# rgbpi-sch.net
KiCad netlist of a schematic drawn in EAGLE
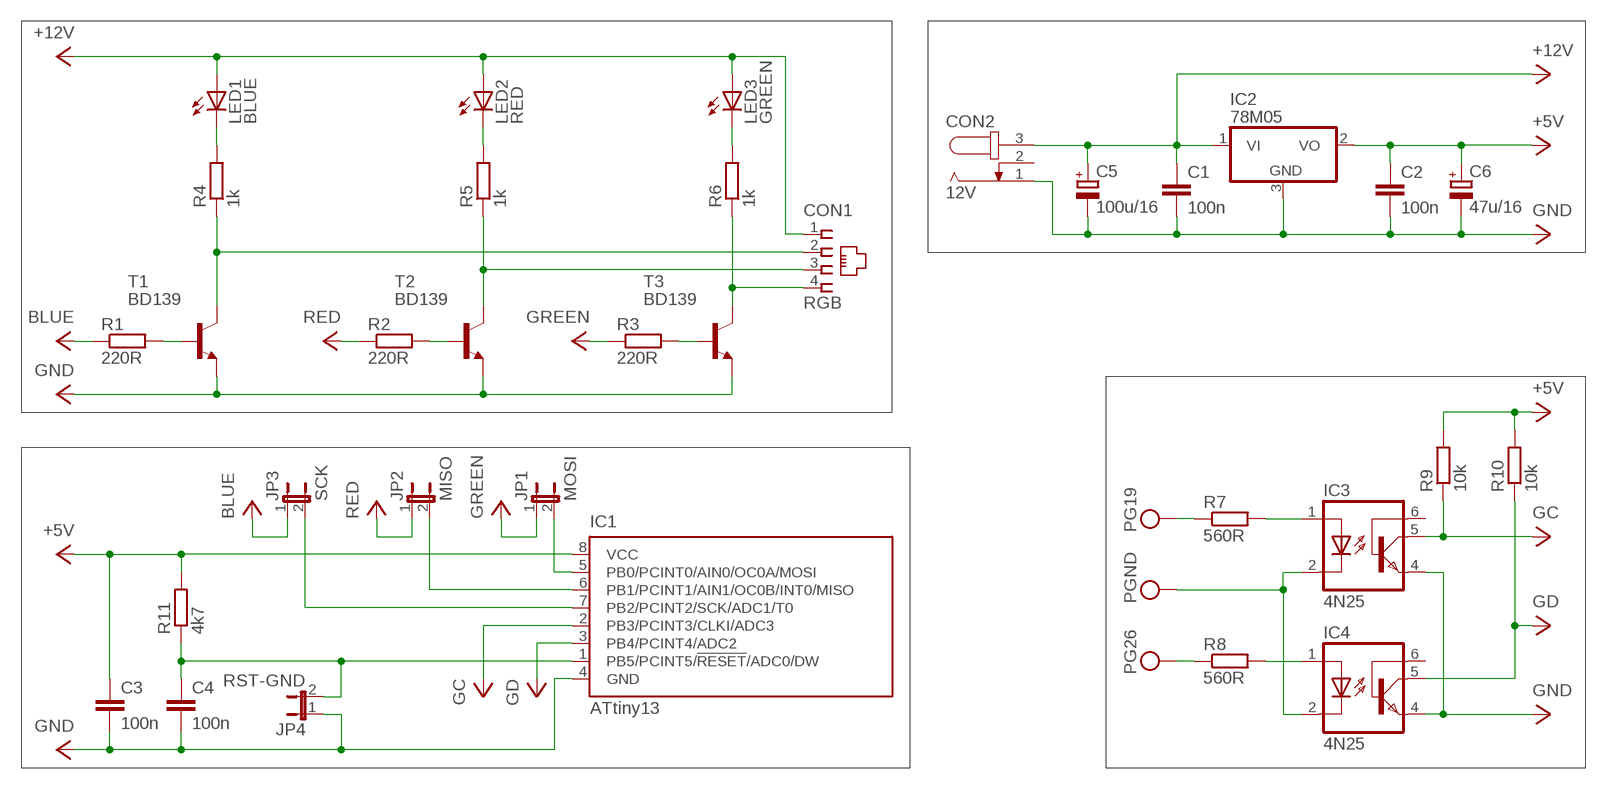
[diagram p0: schematic, sheet 1]

(export (version "E")
  (design (tool "Eeschema 10.0.6"))
  (components
    (comp (ref "C1")
      (value "100n")
      (footprint "eagle-import:C2.5-3")
      (libsource (lib "eagle-import") (part "C2,5-3"))
    )
    (comp (ref "C2")
      (value "100n")
      (footprint "eagle-import:C2.5-3")
      (libsource (lib "eagle-import") (part "C2,5-3"))
    )
    (comp (ref "C3")
      (value "100n")
      (footprint "eagle-import:C2.5-3")
      (libsource (lib "eagle-import") (part "C2,5-3"))
    )
    (comp (ref "C4")
      (value "100n")
      (footprint "eagle-import:C2.5-3")
      (libsource (lib "eagle-import") (part "C2,5-3"))
    )
    (comp (ref "C5")
      (value "100u/16")
      (footprint "eagle-import:085CS_1AR")
      (libsource (lib "eagle-import") (part "CPOL-EU085CS-1AR"))
    )
    (comp (ref "C6")
      (value "47u/16")
      (footprint "eagle-import:085CS_1AR")
      (libsource (lib "eagle-import") (part "CPOL-EU085CS-1AR"))
    )
    (comp (ref "CON1")
      (value "RGB")
      (footprint "eagle-import:215875-3")
      (libsource (lib "eagle-import") (part "215875-3"))
    )
    (comp (ref "CON2")
      (value "12V")
      (footprint "eagle-import:SPC4077")
      (libsource (lib "eagle-import") (part "JACK-PLUG0"))
    )
    (comp (ref "IC1")
      (value "ATtiny13")
      (footprint "eagle-import:8S1")
      (fields (field (name "MPN") "ATTINY13-20SSU"))
      (libsource (lib "eagle-import") (part "TINY13SSU-20"))
    )
    (comp (ref "IC2")
      (value "78M05")
      (footprint "eagle-import:TO252")
      (libsource (lib "eagle-import") (part "78DT05"))
    )
    (comp (ref "IC3")
      (value "4N25")
      (footprint "eagle-import:DIL06")
      (fields (field (name "MPN") "4N25-M"))
      (libsource (lib "eagle-import") (part "4N?M25"))
    )
    (comp (ref "IC4")
      (value "4N25")
      (footprint "eagle-import:DIL06")
      (fields (field (name "MPN") "4N25-M"))
      (libsource (lib "eagle-import") (part "4N?M25"))
    )
    (comp (ref "JP1")
      (value "MOSI")
      (footprint "eagle-import:JP1")
      (libsource (lib "eagle-import") (part "JP1E"))
    )
    (comp (ref "JP2")
      (value "MISO")
      (footprint "eagle-import:JP1")
      (libsource (lib "eagle-import") (part "JP1E"))
    )
    (comp (ref "JP3")
      (value "SCK")
      (footprint "eagle-import:JP1")
      (libsource (lib "eagle-import") (part "JP1E"))
    )
    (comp (ref "JP4")
      (value "RST-GND")
      (footprint "eagle-import:JP1")
      (libsource (lib "eagle-import") (part "JP1E"))
    )
    (comp (ref "LED1")
      (value "BLUE")
      (footprint "eagle-import:W57B")
      (libsource (lib "eagle-import") (part "W57BLA"))
    )
    (comp (ref "LED2")
      (value "RED")
      (footprint "eagle-import:W57B")
      (libsource (lib "eagle-import") (part "W57BLA"))
    )
    (comp (ref "LED3")
      (value "GREEN")
      (footprint "eagle-import:W57B")
      (libsource (lib "eagle-import") (part "W57BLA"))
    )
    (comp (ref "R1")
      (value "220R")
      (footprint "eagle-import:R0805")
      (libsource (lib "eagle-import") (part "R"))
    )
    (comp (ref "R2")
      (value "220R")
      (footprint "eagle-import:R0805")
      (libsource (lib "eagle-import") (part "R"))
    )
    (comp (ref "R3")
      (value "220R")
      (footprint "eagle-import:R0805")
      (libsource (lib "eagle-import") (part "R"))
    )
    (comp (ref "R4")
      (value "1k")
      (footprint "eagle-import:R0805")
      (libsource (lib "eagle-import") (part "R"))
    )
    (comp (ref "R5")
      (value "1k")
      (footprint "eagle-import:R0805")
      (libsource (lib "eagle-import") (part "R"))
    )
    (comp (ref "R6")
      (value "1k")
      (footprint "eagle-import:R0805")
      (libsource (lib "eagle-import") (part "R"))
    )
    (comp (ref "R7")
      (value "560R")
      (footprint "eagle-import:R0805")
      (libsource (lib "eagle-import") (part "R"))
    )
    (comp (ref "R8")
      (value "560R")
      (footprint "eagle-import:R0805")
      (libsource (lib "eagle-import") (part "R"))
    )
    (comp (ref "R9")
      (value "10k")
      (footprint "eagle-import:R0805")
      (libsource (lib "eagle-import") (part "R"))
    )
    (comp (ref "R10")
      (value "10k")
      (footprint "eagle-import:R0805")
      (libsource (lib "eagle-import") (part "R"))
    )
    (comp (ref "R11")
      (value "4k7")
      (footprint "eagle-import:R0805")
      (libsource (lib "eagle-import") (part "R"))
    )
    (comp (ref "T1")
      (value "BD139")
      (footprint "eagle-import:TO126")
      (libsource (lib "eagle-import") (part "BD139"))
    )
    (comp (ref "T2")
      (value "BD139")
      (footprint "eagle-import:TO126")
      (libsource (lib "eagle-import") (part "BD139"))
    )
    (comp (ref "T3")
      (value "BD139")
      (footprint "eagle-import:TO126")
      (libsource (lib "eagle-import") (part "BD139"))
    )
  )
  (nets
    (net (code "1") (name "+12V") (class "Default")
      (node (ref "C1") (pin "1") (pinfunction "1_1") (pintype "passive"))
      (node (ref "C1") (pin "2") (pinfunction "2_2") (pintype "passive"))
      (node (ref "C2") (pin "1") (pinfunction "1_1") (pintype "passive"))
      (node (ref "C2") (pin "2") (pinfunction "2_2") (pintype "passive"))
      (node (ref "C3") (pin "1") (pinfunction "1_1") (pintype "passive"))
      (node (ref "C3") (pin "2") (pinfunction "2_2") (pintype "passive"))
      (node (ref "C4") (pin "2") (pinfunction "2_2") (pintype "passive"))
      (node (ref "C5") (pin "+") (pinfunction "+_+") (pintype "passive"))
      (node (ref "C5") (pin "-") (pinfunction "-_-") (pintype "passive"))
      (node (ref "C6") (pin "+") (pinfunction "+_+") (pintype "passive"))
      (node (ref "C6") (pin "-") (pinfunction "-_-") (pintype "passive"))
      (node (ref "CON1") (pin "1") (pinfunction "1_1") (pintype "passive"))
      (node (ref "CON2") (pin "1") (pinfunction "1_1") (pintype "passive"))
      (node (ref "CON2") (pin "3") (pinfunction "3_3") (pintype "passive"))
      (node (ref "IC1") (pin "2") (pinfunction "PB3/PCINT3/CLKI/ADC3_2") (pintype "bidirectional"))
      (node (ref "IC1") (pin "3") (pinfunction "PB4/PCINT4/ADC2_3") (pintype "bidirectional"))
      (node (ref "IC1") (pin "4") (pinfunction "GND_4") (pintype "power_in"))
      (node (ref "IC1") (pin "8") (pinfunction "VCC_8") (pintype "power_in"))
      (node (ref "IC2") (pin "1") (pinfunction "VI_1") (pintype "input"))
      (node (ref "IC2") (pin "2") (pinfunction "VO_2") (pintype "passive"))
      (node (ref "IC2") (pin "3") (pinfunction "GND_3") (pintype "passive"))
      (node (ref "IC3") (pin "2") (pinfunction "C_2") (pintype "passive"))
      (node (ref "IC3") (pin "4") (pinfunction "EMI_4") (pintype "passive"))
      (node (ref "IC3") (pin "5") (pinfunction "COL_5") (pintype "passive"))
      (node (ref "IC4") (pin "2") (pinfunction "C_2") (pintype "passive"))
      (node (ref "IC4") (pin "4") (pinfunction "EMI_4") (pintype "passive"))
      (node (ref "IC4") (pin "5") (pinfunction "COL_5") (pintype "passive"))
      (node (ref "JP1") (pin "1") (pinfunction "1_1") (pintype "passive"))
      (node (ref "JP2") (pin "1") (pinfunction "1_1") (pintype "passive"))
      (node (ref "JP3") (pin "1") (pinfunction "1_1") (pintype "passive"))
      (node (ref "JP4") (pin "1") (pinfunction "1_1") (pintype "passive"))
      (node (ref "LED1") (pin "A") (pinfunction "A_A") (pintype "passive"))
      (node (ref "LED2") (pin "A") (pinfunction "A_A") (pintype "passive"))
      (node (ref "LED3") (pin "A") (pinfunction "A_A") (pintype "passive"))
      (node (ref "R1") (pin "1") (pinfunction "1_1") (pintype "passive"))
      (node (ref "R10") (pin "1") (pinfunction "1_1") (pintype "passive"))
      (node (ref "R10") (pin "2") (pinfunction "2_2") (pintype "passive"))
      (node (ref "R11") (pin "2") (pinfunction "2_2") (pintype "passive"))
      (node (ref "R2") (pin "1") (pinfunction "1_1") (pintype "passive"))
      (node (ref "R3") (pin "1") (pinfunction "1_1") (pintype "passive"))
      (node (ref "R7") (pin "1") (pinfunction "1_1") (pintype "passive"))
      (node (ref "R8") (pin "1") (pinfunction "1_1") (pintype "passive"))
      (node (ref "R9") (pin "1") (pinfunction "1_1") (pintype "passive"))
      (node (ref "R9") (pin "2") (pinfunction "2_2") (pintype "passive"))
      (node (ref "T1") (pin "1") (pinfunction "E_1") (pintype "passive"))
      (node (ref "T2") (pin "1") (pinfunction "E_1") (pintype "passive"))
      (node (ref "T3") (pin "1") (pinfunction "E_1") (pintype "passive"))
    )
    (net (code "2") (name "Net-(IC1-PB0{slash}PCINT0{slash}AIN0{slash}OC0A{slash}MOSI)") (class "Default")
      (node (ref "IC1") (pin "5") (pinfunction "PB0/PCINT0/AIN0/OC0A/MOSI_5") (pintype "bidirectional"))
      (node (ref "JP1") (pin "2") (pinfunction "2_2") (pintype "passive"))
    )
    (net (code "3") (name "Net-(IC1-PB1{slash}PCINT1{slash}AIN1{slash}OC0B{slash}INT0{slash}MISO)") (class "Default")
      (node (ref "IC1") (pin "6") (pinfunction "PB1/PCINT1/AIN1/OC0B/INT0/MISO_6") (pintype "bidirectional"))
      (node (ref "JP2") (pin "2") (pinfunction "2_2") (pintype "passive"))
    )
    (net (code "4") (name "Net-(IC1-PB2{slash}PCINT2{slash}SCK{slash}ADC1{slash}T0)") (class "Default")
      (node (ref "IC1") (pin "7") (pinfunction "PB2/PCINT2/SCK/ADC1/T0_7") (pintype "bidirectional"))
      (node (ref "JP3") (pin "2") (pinfunction "2_2") (pintype "passive"))
    )
    (net (code "5") (name "Net-(IC1-PB5{slash}PCINT5{slash}~{RESET}{slash}ADC0{slash}DW)") (class "Default")
      (node (ref "C4") (pin "1") (pinfunction "1_1") (pintype "passive"))
      (node (ref "IC1") (pin "1") (pinfunction "PB5/PCINT5/~{RESET}/ADC0/DW_1") (pintype "bidirectional"))
      (node (ref "JP4") (pin "2") (pinfunction "2_2") (pintype "passive"))
      (node (ref "R11") (pin "1") (pinfunction "1_1") (pintype "passive"))
    )
    (net (code "6") (name "Net-(IC3-A)") (class "Default")
      (node (ref "IC3") (pin "1") (pinfunction "A_1") (pintype "passive"))
      (node (ref "R7") (pin "2") (pinfunction "2_2") (pintype "passive"))
    )
    (net (code "7") (name "Net-(IC4-A)") (class "Default")
      (node (ref "IC4") (pin "1") (pinfunction "A_1") (pintype "passive"))
      (node (ref "R8") (pin "2") (pinfunction "2_2") (pintype "passive"))
    )
    (net (code "8") (name "Net-(LED1-C-PadC@1)") (class "Default")
      (node (ref "LED1") (pin "C") (pinfunction "C_C") (pintype "passive"))
      (node (ref "LED1") (pin "C@1") (pinfunction "C_C@1") (pintype "passive"))
      (node (ref "LED1") (pin "C@2") (pinfunction "C_C@2") (pintype "passive"))
      (node (ref "LED1") (pin "C@3") (pinfunction "C_C@3") (pintype "passive"))
      (node (ref "LED1") (pin "C@4") (pinfunction "C_C@4") (pintype "passive"))
      (node (ref "LED1") (pin "C@5") (pinfunction "C_C@5") (pintype "passive"))
      (node (ref "R4") (pin "2") (pinfunction "2_2") (pintype "passive"))
    )
    (net (code "9") (name "Net-(LED2-C-PadC@1)") (class "Default")
      (node (ref "LED2") (pin "C") (pinfunction "C_C") (pintype "passive"))
      (node (ref "LED2") (pin "C@1") (pinfunction "C_C@1") (pintype "passive"))
      (node (ref "LED2") (pin "C@2") (pinfunction "C_C@2") (pintype "passive"))
      (node (ref "LED2") (pin "C@3") (pinfunction "C_C@3") (pintype "passive"))
      (node (ref "LED2") (pin "C@4") (pinfunction "C_C@4") (pintype "passive"))
      (node (ref "LED2") (pin "C@5") (pinfunction "C_C@5") (pintype "passive"))
      (node (ref "R5") (pin "2") (pinfunction "2_2") (pintype "passive"))
    )
    (net (code "10") (name "Net-(LED3-C-PadC@1)") (class "Default")
      (node (ref "LED3") (pin "C") (pinfunction "C_C") (pintype "passive"))
      (node (ref "LED3") (pin "C@1") (pinfunction "C_C@1") (pintype "passive"))
      (node (ref "LED3") (pin "C@2") (pinfunction "C_C@2") (pintype "passive"))
      (node (ref "LED3") (pin "C@3") (pinfunction "C_C@3") (pintype "passive"))
      (node (ref "LED3") (pin "C@4") (pinfunction "C_C@4") (pintype "passive"))
      (node (ref "LED3") (pin "C@5") (pinfunction "C_C@5") (pintype "passive"))
      (node (ref "R6") (pin "2") (pinfunction "2_2") (pintype "passive"))
    )
    (net (code "11") (name "Net-(T1-B)") (class "Default")
      (node (ref "R1") (pin "2") (pinfunction "2_2") (pintype "passive"))
      (node (ref "T1") (pin "3") (pinfunction "B_3") (pintype "passive"))
    )
    (net (code "12") (name "Net-(T1-C)") (class "Default")
      (node (ref "CON1") (pin "2") (pinfunction "2_2") (pintype "passive"))
      (node (ref "R4") (pin "1") (pinfunction "1_1") (pintype "passive"))
      (node (ref "T1") (pin "2") (pinfunction "C_2") (pintype "passive"))
    )
    (net (code "13") (name "Net-(T2-B)") (class "Default")
      (node (ref "R2") (pin "2") (pinfunction "2_2") (pintype "passive"))
      (node (ref "T2") (pin "3") (pinfunction "B_3") (pintype "passive"))
    )
    (net (code "14") (name "Net-(T2-C)") (class "Default")
      (node (ref "CON1") (pin "3") (pinfunction "3_3") (pintype "passive"))
      (node (ref "R5") (pin "1") (pinfunction "1_1") (pintype "passive"))
      (node (ref "T2") (pin "2") (pinfunction "C_2") (pintype "passive"))
    )
    (net (code "15") (name "Net-(T3-B)") (class "Default")
      (node (ref "R3") (pin "2") (pinfunction "2_2") (pintype "passive"))
      (node (ref "T3") (pin "3") (pinfunction "B_3") (pintype "passive"))
    )
    (net (code "16") (name "Net-(T3-C)") (class "Default")
      (node (ref "CON1") (pin "4") (pinfunction "4_4") (pintype "passive"))
      (node (ref "R6") (pin "1") (pinfunction "1_1") (pintype "passive"))
      (node (ref "T3") (pin "2") (pinfunction "C_2") (pintype "passive"))
    )
    (net (code "17") (name "unconnected-(CON2-Pad2)") (class "Default")
      (node (ref "CON2") (pin "2") (pinfunction "2_2") (pintype "passive"))
    )
    (net (code "18") (name "unconnected-(IC3-BAS-Pad6)") (class "Default")
      (node (ref "IC3") (pin "6") (pinfunction "BAS_6") (pintype "passive"))
    )
    (net (code "19") (name "unconnected-(IC4-BAS-Pad6)") (class "Default")
      (node (ref "IC4") (pin "6") (pinfunction "BAS_6") (pintype "passive"))
    )
  )
)
